# MD.net
KiCad netlist of a schematic drawn in EAGLE
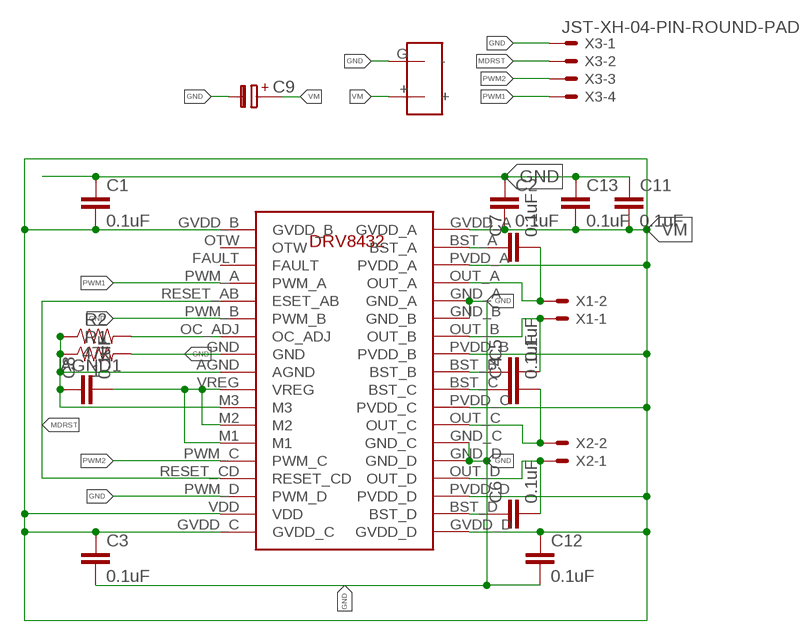
[diagram p0: schematic, sheet 1]

(export (version "E")
  (design (tool "Eeschema 10.0.6"))
  (components
    (comp (ref "C1")
      (value "0.1uF")
      (footprint "eagle-import:0603")
      (libsource (lib "eagle-import") (part "0.1UF-0603-100V-10%"))
    )
    (comp (ref "C2")
      (value "0.1uF")
      (footprint "eagle-import:0603")
      (libsource (lib "eagle-import") (part "0.1UF-0603-100V-10%"))
    )
    (comp (ref "C3")
      (value "0.1uF")
      (footprint "eagle-import:0603")
      (libsource (lib "eagle-import") (part "0.1UF-0603-100V-10%"))
    )
    (comp (ref "C4")
      (value "0.1uF")
      (footprint "eagle-import:0603")
      (libsource (lib "eagle-import") (part "0.1UF-0603-25V-(+80/-20%)"))
    )
    (comp (ref "C5")
      (value "0.1uF")
      (footprint "eagle-import:0603")
      (libsource (lib "eagle-import") (part "0.1UF-0603-25V-(+80/-20%)"))
    )
    (comp (ref "C6")
      (value "0.1uF")
      (footprint "eagle-import:0603")
      (libsource (lib "eagle-import") (part "0.1UF-0603-25V-(+80/-20%)"))
    )
    (comp (ref "C7")
      (value "0.1uF")
      (footprint "eagle-import:0603")
      (libsource (lib "eagle-import") (part "0.1UF-0603-25V-(+80/-20%)"))
    )
    (comp (ref "C8")
      (value "0.1uF")
      (footprint "eagle-import:0603")
      (libsource (lib "eagle-import") (part "0.1UF-0603-25V-(+80/-20%)"))
    )
    (comp (ref "C9")
      (value "C-PR-3,5X8")
      (footprint "eagle-import:E3,5-8")
      (libsource (lib "eagle-import") (part "C-PR-3,5X8"))
    )
    (comp (ref "C11")
      (value "0.1uF")
      (footprint "eagle-import:0603")
      (libsource (lib "eagle-import") (part "0.1UF-0603-25V-(+80/-20%)"))
    )
    (comp (ref "C12")
      (value "0.1uF")
      (footprint "eagle-import:0603")
      (libsource (lib "eagle-import") (part "0.1UF-0603-100V-10%"))
    )
    (comp (ref "C13")
      (value "0.1uF")
      (footprint "eagle-import:0603")
      (libsource (lib "eagle-import") (part "0.1UF-0603-100V-10%"))
    )
    (comp (ref "R1")
      (value "1")
      (footprint "eagle-import:0603")
      (libsource (lib "eagle-import") (part "0OHM-0603-1/10W-5%"))
    )
    (comp (ref "R2")
      (value "47k")
      (footprint "eagle-import:0603")
      (libsource (lib "eagle-import") (part "47KOHM-0603-1/10W-1%"))
    )
    (comp (ref "U$1")
      (value "DRV8432DKDR")
      (footprint "eagle-import:HSSOP-36")
      (libsource (lib "eagle-import") (part "DRV8432DKDR"))
    )
    (comp (ref "U$2")
      (value "BAT")
      (footprint "eagle-import:BAT")
      (libsource (lib "eagle-import") (part "BAT"))
    )
    (comp (ref "X1")
      (value "JST-XH-02-PIN-LONG-PAD")
      (footprint "eagle-import:JST-XH-02-PACKAGE-LONG-PAD")
      (libsource (lib "eagle-import") (part "JST-XH-02-PIN-LONG-PAD"))
    )
    (comp (ref "X2")
      (value "JST-XH-02-PIN-LONG-PAD")
      (footprint "eagle-import:JST-XH-02-PACKAGE-LONG-PAD")
      (libsource (lib "eagle-import") (part "JST-XH-02-PIN-LONG-PAD"))
    )
    (comp (ref "X3")
      (value "JST-XH-04-PIN-ROUND-PAD")
      (footprint "eagle-import:JST-XH-04-PACKAGE-ROUND-PAD")
      (libsource (lib "eagle-import") (part "JST-XH-04-PIN-ROUND-PAD"))
    )
  )
  (nets
    (net (code "1") (name "/AGND1") (class "Default")
      (node (ref "C8") (pin "1") (pinfunction "1_1") (pintype "passive"))
      (node (ref "R1") (pin "1") (pinfunction "1_1") (pintype "passive"))
      (node (ref "R2") (pin "1") (pinfunction "1_1") (pintype "passive"))
      (node (ref "U$1") (pin "AGND") (pinfunction "AGND_AGND") (pintype "bidirectional"))
      (node (ref "U$1") (pin "M3") (pinfunction "M3_M3") (pintype "bidirectional"))
    )
    (net (code "2") (name "GND") (class "Default")
      (node (ref "C1") (pin "1") (pinfunction "1_1") (pintype "passive"))
      (node (ref "C11") (pin "1") (pinfunction "1_1") (pintype "passive"))
      (node (ref "C12") (pin "2") (pinfunction "2_2") (pintype "passive"))
      (node (ref "C13") (pin "1") (pinfunction "1_1") (pintype "passive"))
      (node (ref "C2") (pin "1") (pinfunction "1_1") (pintype "passive"))
      (node (ref "C3") (pin "2") (pinfunction "2_2") (pintype "passive"))
      (node (ref "C9") (pin "-") (pinfunction "-_-") (pintype "passive"))
      (node (ref "R1") (pin "2") (pinfunction "2_2") (pintype "passive"))
      (node (ref "U$1") (pin "GND") (pinfunction "GND_GND") (pintype "bidirectional"))
      (node (ref "U$1") (pin "GND_A") (pinfunction "GND_A_GND_A") (pintype "bidirectional"))
      (node (ref "U$1") (pin "GND_B") (pinfunction "GND_B_GND_B") (pintype "bidirectional"))
      (node (ref "U$1") (pin "GND_C") (pinfunction "GND_C_GND_C") (pintype "bidirectional"))
      (node (ref "U$1") (pin "GND_D") (pinfunction "GND_D_GND_D") (pintype "bidirectional"))
      (node (ref "U$1") (pin "PWM_B") (pinfunction "PWM_B_PWM_B") (pintype "bidirectional"))
      (node (ref "U$1") (pin "PWM_D") (pinfunction "PWM_D_PWM_D") (pintype "bidirectional"))
      (node (ref "U$2") (pin "G") (pinfunction "-_G") (pintype "bidirectional"))
      (node (ref "X3") (pin "1") (pinfunction "S_1") (pintype "passive"))
    )
    (net (code "3") (name "MDRST") (class "Default")
      (node (ref "U$1") (pin "RESET_AB") (pinfunction "ESET_AB_RESET_AB") (pintype "bidirectional"))
      (node (ref "U$1") (pin "RESET_CD") (pinfunction "RESET_CD_RESET_CD") (pintype "bidirectional"))
      (node (ref "X3") (pin "2") (pinfunction "S_2") (pintype "passive"))
    )
    (net (code "4") (name "Net-(C4-Pad1)") (class "Default")
      (node (ref "C4") (pin "1") (pinfunction "1_1") (pintype "passive"))
      (node (ref "U$1") (pin "BST_C") (pinfunction "BST_C_BST_C") (pintype "bidirectional"))
    )
    (net (code "5") (name "Net-(C5-Pad1)") (class "Default")
      (node (ref "C5") (pin "1") (pinfunction "1_1") (pintype "passive"))
      (node (ref "U$1") (pin "BST_B") (pinfunction "BST_B_BST_B") (pintype "bidirectional"))
    )
    (net (code "6") (name "Net-(C6-Pad1)") (class "Default")
      (node (ref "C6") (pin "1") (pinfunction "1_1") (pintype "passive"))
      (node (ref "U$1") (pin "BST_D") (pinfunction "BST_D_BST_D") (pintype "bidirectional"))
    )
    (net (code "7") (name "Net-(C7-Pad1)") (class "Default")
      (node (ref "C7") (pin "1") (pinfunction "1_1") (pintype "passive"))
      (node (ref "U$1") (pin "BST_A") (pinfunction "BST_A_BST_A") (pintype "bidirectional"))
    )
    (net (code "8") (name "Net-(C8-Pad2)") (class "Default")
      (node (ref "C8") (pin "2") (pinfunction "2_2") (pintype "passive"))
      (node (ref "U$1") (pin "M1") (pinfunction "M1_M1") (pintype "bidirectional"))
      (node (ref "U$1") (pin "M2") (pinfunction "M2_M2") (pintype "bidirectional"))
      (node (ref "U$1") (pin "VREG") (pinfunction "VREG_VREG") (pintype "bidirectional"))
    )
    (net (code "9") (name "Net-(R2-Pad2)") (class "Default")
      (node (ref "R2") (pin "2") (pinfunction "2_2") (pintype "passive"))
      (node (ref "U$1") (pin "OC_ADJ") (pinfunction "OC_ADJ_OC_ADJ") (pintype "bidirectional"))
    )
    (net (code "10") (name "Net-(X1A-S)") (class "Default")
      (node (ref "C5") (pin "2") (pinfunction "2_2") (pintype "passive"))
      (node (ref "U$1") (pin "OUT_B") (pinfunction "OUT_B_OUT_B") (pintype "bidirectional"))
      (node (ref "X1") (pin "1") (pinfunction "S_1") (pintype "passive"))
    )
    (net (code "11") (name "Net-(X1B-S)") (class "Default")
      (node (ref "C7") (pin "2") (pinfunction "2_2") (pintype "passive"))
      (node (ref "U$1") (pin "OUT_A") (pinfunction "OUT_A_OUT_A") (pintype "bidirectional"))
      (node (ref "X1") (pin "2") (pinfunction "S_2") (pintype "passive"))
    )
    (net (code "12") (name "Net-(X2A-S)") (class "Default")
      (node (ref "C6") (pin "2") (pinfunction "2_2") (pintype "passive"))
      (node (ref "U$1") (pin "OUT_D") (pinfunction "OUT_D_OUT_D") (pintype "bidirectional"))
      (node (ref "X2") (pin "1") (pinfunction "S_1") (pintype "passive"))
    )
    (net (code "13") (name "Net-(X2B-S)") (class "Default")
      (node (ref "C4") (pin "2") (pinfunction "2_2") (pintype "passive"))
      (node (ref "U$1") (pin "OUT_C") (pinfunction "OUT_C_OUT_C") (pintype "bidirectional"))
      (node (ref "X2") (pin "2") (pinfunction "S_2") (pintype "passive"))
    )
    (net (code "14") (name "PWM1") (class "Default")
      (node (ref "U$1") (pin "PWM_A") (pinfunction "PWM_A_PWM_A") (pintype "bidirectional"))
      (node (ref "X3") (pin "4") (pinfunction "S_4") (pintype "passive"))
    )
    (net (code "15") (name "PWM2") (class "Default")
      (node (ref "U$1") (pin "PWM_C") (pinfunction "PWM_C_PWM_C") (pintype "bidirectional"))
      (node (ref "X3") (pin "3") (pinfunction "S_3") (pintype "passive"))
    )
    (net (code "16") (name "VM") (class "Default")
      (node (ref "C1") (pin "2") (pinfunction "2_2") (pintype "passive"))
      (node (ref "C11") (pin "2") (pinfunction "2_2") (pintype "passive"))
      (node (ref "C12") (pin "1") (pinfunction "1_1") (pintype "passive"))
      (node (ref "C13") (pin "2") (pinfunction "2_2") (pintype "passive"))
      (node (ref "C2") (pin "2") (pinfunction "2_2") (pintype "passive"))
      (node (ref "C3") (pin "1") (pinfunction "1_1") (pintype "passive"))
      (node (ref "C9") (pin "+") (pinfunction "+_+") (pintype "passive"))
      (node (ref "U$1") (pin "GVDD_A") (pinfunction "GVDD_A_GVDD_A") (pintype "bidirectional"))
      (node (ref "U$1") (pin "GVDD_B") (pinfunction "GVDD_B_GVDD_B") (pintype "bidirectional"))
      (node (ref "U$1") (pin "GVDD_C") (pinfunction "GVDD_C_GVDD_C") (pintype "bidirectional"))
      (node (ref "U$1") (pin "GVDD_D") (pinfunction "GVDD_D_GVDD_D") (pintype "bidirectional"))
      (node (ref "U$1") (pin "PVDD_A") (pinfunction "PVDD_A_PVDD_A") (pintype "bidirectional"))
      (node (ref "U$1") (pin "PVDD_B") (pinfunction "PVDD_B_PVDD_B") (pintype "bidirectional"))
      (node (ref "U$1") (pin "PVDD_C") (pinfunction "PVDD_C_PVDD_C") (pintype "bidirectional"))
      (node (ref "U$1") (pin "PVDD_D") (pinfunction "PVDD_D_PVDD_D") (pintype "bidirectional"))
      (node (ref "U$1") (pin "VDD") (pinfunction "VDD_VDD") (pintype "bidirectional"))
      (node (ref "U$2") (pin "+") (pinfunction "+_+") (pintype "bidirectional"))
    )
    (net (code "17") (name "unconnected-(U$1-PadFAULT)") (class "Default")
      (node (ref "U$1") (pin "FAULT") (pinfunction "FAULT_FAULT") (pintype "bidirectional"))
    )
    (net (code "18") (name "unconnected-(U$1-PadOTW)") (class "Default")
      (node (ref "U$1") (pin "OTW") (pinfunction "OTW_OTW") (pintype "bidirectional"))
    )
  )
)
